# 1_-_Top.net
KiCad netlist of a schematic drawn in Altium Designer
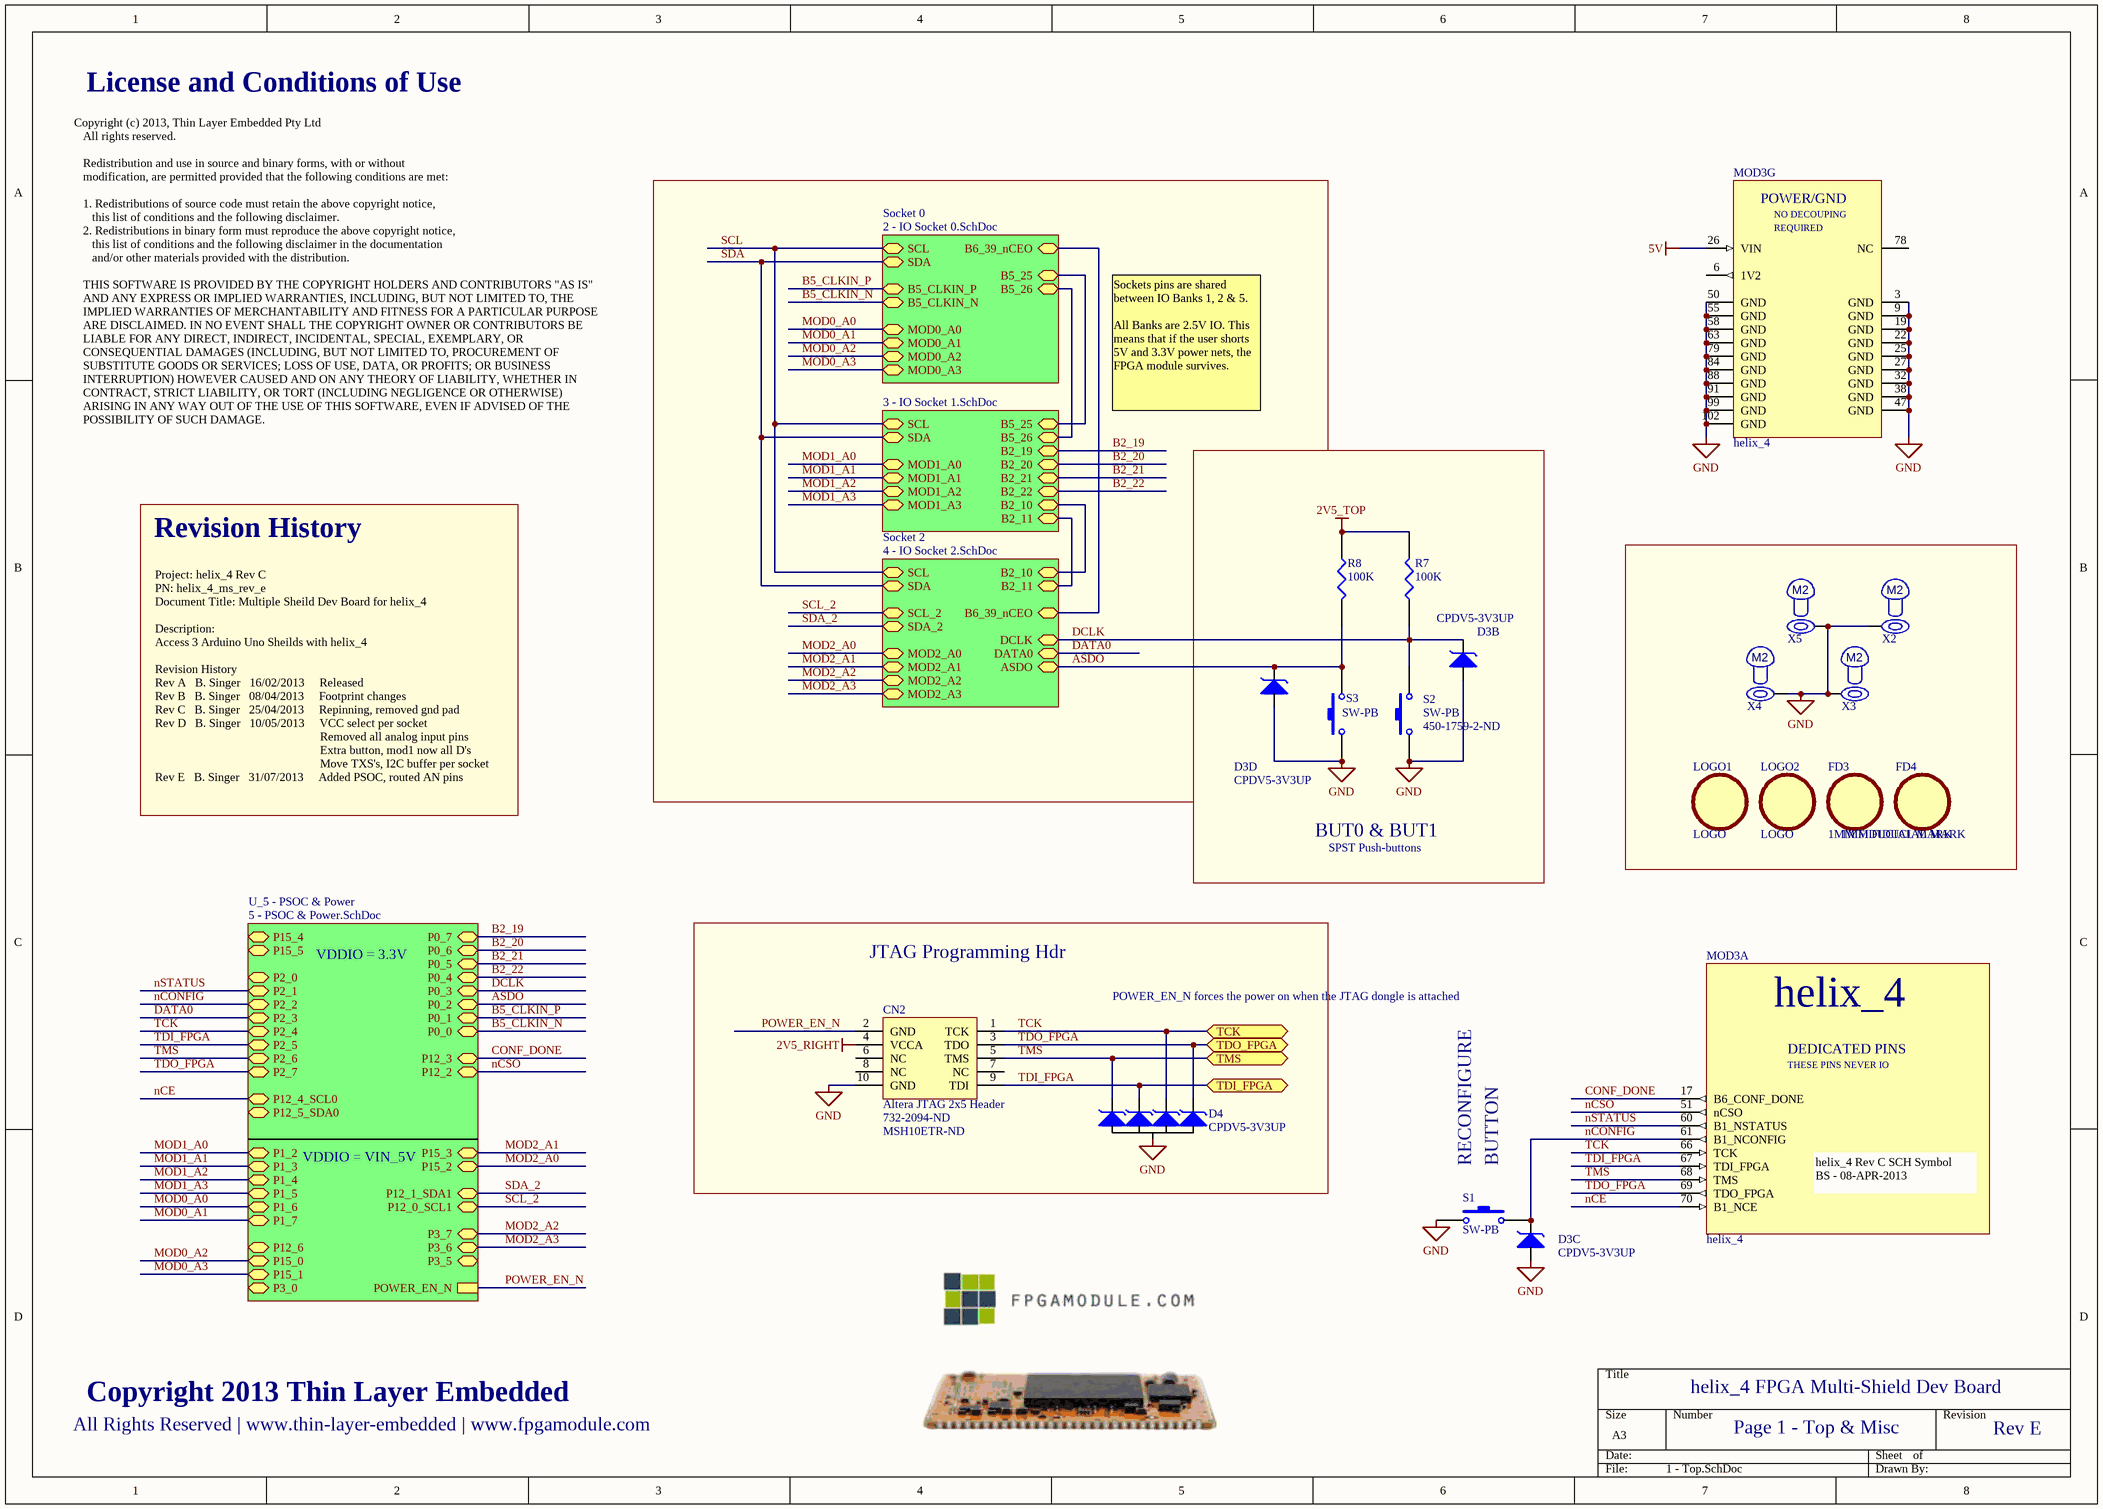
[diagram p0: 1 - Top.SchDoc]

(export (version "E")
  (design (tool "Eeschema 10.0.6"))
  (components
    (comp (ref "CN2")
      (value "Altera JTAG 2x5 Header")
      (footprint "BOXHDR2X5")
      (description "Header, 5-Pin, Dual row")
      (fields
        (field (name "MANUFACTURER") "Wurth Electronics Inc")
        (field (name "MANUFACTURER PART NUMBER") "61201021621")
        (field (name "SUPPLIER PART NUMBER 1") "732-2094-ND")
        (field (name "SUPPLIER PART NUMBER 2") "MSH10ETR-ND")
        (field (name "PUBLISHER") "Altium Limited")
      )
      (libsource (lib "master_library") (part "Altera JTAG 2x5 Header"))
    )
    (comp (ref "D3")
      (value "CPDV5-3V3UP")
      (footprint "sot-353")
      (description "4CH ESD DIODE 3V3/3.5V")
      (libsource (lib "master_library") (part "4CH ESD DIODE (SPLIT)"))
    )
    (comp (ref "D4")
      (value "CPDV5-3V3UP")
      (footprint "SOT-353")
      (description "4CH ESD DIODE 3V3/3.5V")
      (libsource (lib "master_library") (part "4CH ESD DIODE"))
    )
    (comp (ref "FD3") (value "1MM FIDUCIAL MARK") (footprint "FID_1MM") (libsource (lib "OB_1") (part "FID")))
    (comp (ref "FD4") (value "1MM FIDUCIAL MARK") (footprint "FID_1MM") (libsource (lib "OB_1") (part "FID")))
    (comp (ref "LOGO1") (value "LOGO") (footprint "LOGO_LARGE") (libsource (lib "OB_1") (part "FID")))
    (comp (ref "LOGO2") (value "LOGO") (footprint "LOGO_LARGE") (libsource (lib "OB_1") (part "FID")))
    (comp (ref "MOD3")
      (value "helix_4")
      (footprint "HELIX_4_LCC104_HOST")
      (libsource (lib "master_library") (part "helix_4 Rev C Module"))
    )
    (comp (ref "R7") (value "100K") (footprint "0805") (libsource (lib "*") (part "RES1")))
    (comp (ref "R8") (value "100K") (footprint "0805") (libsource (lib "*") (part "RES1")))
    (comp (ref "S1")
      (value "SW-PB")
      (footprint "FSM4JSMA")
      (description "Switch")
      (fields (field (name "PUBLISHER") "Altium Limited"))
      (libsource (lib "Miscellaneous Devices") (part "SW-PB"))
    )
    (comp (ref "S2")
      (value "SW-PB")
      (footprint "FSM4JSMA")
      (description "Switch")
      (fields (field (name "PUBLISHER") "Altium Limited"))
      (libsource (lib "Miscellaneous Devices") (part "SW-PB"))
    )
    (comp (ref "S3")
      (value "SW-PB")
      (footprint "FSM4JSMA")
      (description "Switch")
      (fields
        (field (name "SUPPLIER PART NUMBER 1") "450-1759-2-ND")
        (field (name "PUBLISHER") "Altium Limited")
      )
      (libsource (lib "Miscellaneous Devices") (part "SW-PB"))
    )
    (comp (ref "X2")
      (value "M2 Mounting Hole")
      (footprint "Mounting_Hole_M3")
      (description "Hole for M3 Screw")
      (libsource (lib "") (part "Mounting_Hole_M2_1"))
    )
    (comp (ref "X3")
      (value "M2 Mounting Hole")
      (footprint "Mounting_Hole_M3")
      (description "Hole for M3 Screw")
      (libsource (lib "") (part "Mounting_Hole_M2_1"))
    )
    (comp (ref "X4")
      (value "M2 Mounting Hole")
      (footprint "Mounting_Hole_M3")
      (description "Hole for M3 Screw")
      (libsource (lib "tea133-sch-2") (part "Mounting_Hole_M2"))
    )
    (comp (ref "X5")
      (value "M2 Mounting Hole")
      (footprint "Mounting_Hole_M3")
      (description "Hole for M3 Screw")
      (libsource (lib "tea133-sch-2") (part "Mounting_Hole_M2"))
    )
  )
  (nets
    (net (code "1") (name "/ASDO") (class "Default")
      (node (ref "D3") (pin "4") (pinfunction "K4_4") (pintype "passive"))
      (node (ref "R8") (pin "2") (pinfunction "2_2") (pintype "passive"))
      (node (ref "S3") (pin "2") (pinfunction "2_2") (pintype "passive"))
    )
    (net (code "13") (name "/CONF_DONE") (class "Default")
      (node (ref "MOD3") (pin "17") (pinfunction "B6_CONF_DONE_17") (pintype "output"))
    )
    (net (code "15") (name "/DCLK") (class "Default")
      (node (ref "D3") (pin "1") (pinfunction "K2_1") (pintype "passive"))
      (node (ref "R7") (pin "2") (pinfunction "2_2") (pintype "passive"))
      (node (ref "S2") (pin "2") (pinfunction "2_2") (pintype "passive"))
    )
    (net (code "35") (name "/POWER_EN_N") (class "Default")
      (node (ref "CN2") (pin "2") (pinfunction "GND_2") (pintype "passive"))
    )
    (net (code "40") (name "/TCK") (class "Default")
      (node (ref "CN2") (pin "1") (pinfunction "TCK_1") (pintype "passive"))
      (node (ref "D4") (pin "5") (pinfunction "K1_5") (pintype "passive"))
      (node (ref "MOD3") (pin "66") (pinfunction "TCK_66") (pintype "input"))
    )
    (net (code "41") (name "/TDI_FPGA") (class "Default")
      (node (ref "CN2") (pin "9") (pinfunction "TDI_9") (pintype "passive"))
      (node (ref "D4") (pin "1") (pinfunction "K2_1") (pintype "passive"))
      (node (ref "MOD3") (pin "67") (pinfunction "TDI_FPGA_67") (pintype "input"))
    )
    (net (code "42") (name "/TDO_FPGA") (class "Default")
      (node (ref "CN2") (pin "3") (pinfunction "TDO_3") (pintype "passive"))
      (node (ref "D4") (pin "4") (pinfunction "K2_4") (pintype "passive"))
      (node (ref "MOD3") (pin "69") (pinfunction "TDO_FPGA_69") (pintype "output"))
    )
    (net (code "43") (name "/TMS") (class "Default")
      (node (ref "CN2") (pin "5") (pinfunction "TMS_5") (pintype "passive"))
      (node (ref "D4") (pin "3") (pinfunction "K1_3") (pintype "passive"))
      (node (ref "MOD3") (pin "68") (pinfunction "TMS_68") (pintype "input"))
    )
    (net (code "44") (name "/nCE") (class "Default")
      (node (ref "MOD3") (pin "70") (pinfunction "B1_NCE_70") (pintype "input"))
    )
    (net (code "45") (name "/nCONFIG") (class "Default")
      (node (ref "D3") (pin "5") (pinfunction "K3_5") (pintype "passive"))
      (node (ref "MOD3") (pin "61") (pinfunction "B1_NCONFIG_61") (pintype "output"))
      (node (ref "S1") (pin "2") (pinfunction "2_2") (pintype "passive"))
    )
    (net (code "46") (name "/nCSO") (class "Default")
      (node (ref "MOD3") (pin "51") (pinfunction "nCSO_51") (pintype "output"))
    )
    (net (code "47") (name "/nSTATUS") (class "Default")
      (node (ref "MOD3") (pin "60") (pinfunction "B1_NSTATUS_60") (pintype "output"))
    )
    (net (code "48") (name "2V5_RIGHT") (class "Default")
      (node (ref "CN2") (pin "4") (pinfunction "VCCA_4") (pintype "passive"))
    )
    (net (code "49") (name "2V5_TOP") (class "Default")
      (node (ref "R7") (pin "1") (pinfunction "1_1") (pintype "passive"))
      (node (ref "R8") (pin "1") (pinfunction "1_1") (pintype "passive"))
    )
    (net (code "50") (name "5V") (class "Default")
      (node (ref "MOD3") (pin "26") (pinfunction "VIN_26") (pintype "input"))
    )
    (net (code "51") (name "GND") (class "Default")
      (node (ref "CN2") (pin "10") (pinfunction "GND_10") (pintype "passive"))
      (node (ref "D3") (pin "2") (pinfunction "A_2") (pintype "passive"))
      (node (ref "D4") (pin "2") (pinfunction "A_2") (pintype "passive"))
      (node (ref "MOD3") (pin "102") (pinfunction "GND_102") (pintype "passive"))
      (node (ref "MOD3") (pin "19") (pinfunction "GND_19") (pintype "passive"))
      (node (ref "MOD3") (pin "22") (pinfunction "GND_22") (pintype "passive"))
      (node (ref "MOD3") (pin "25") (pinfunction "GND_25") (pintype "passive"))
      (node (ref "MOD3") (pin "27") (pinfunction "GND_27") (pintype "passive"))
      (node (ref "MOD3") (pin "3") (pinfunction "GND_3") (pintype "passive"))
      (node (ref "MOD3") (pin "32") (pinfunction "GND_32") (pintype "passive"))
      (node (ref "MOD3") (pin "38") (pinfunction "GND_38") (pintype "passive"))
      (node (ref "MOD3") (pin "47") (pinfunction "GND_47") (pintype "passive"))
      (node (ref "MOD3") (pin "50") (pinfunction "GND_50") (pintype "passive"))
      (node (ref "MOD3") (pin "55") (pinfunction "GND_55") (pintype "passive"))
      (node (ref "MOD3") (pin "58") (pinfunction "GND_58") (pintype "passive"))
      (node (ref "MOD3") (pin "63") (pinfunction "GND_63") (pintype "passive"))
      (node (ref "MOD3") (pin "79") (pinfunction "GND_79") (pintype "passive"))
      (node (ref "MOD3") (pin "84") (pinfunction "GND_84") (pintype "passive"))
      (node (ref "MOD3") (pin "88") (pinfunction "GND_88") (pintype "passive"))
      (node (ref "MOD3") (pin "9") (pinfunction "GND_9") (pintype "passive"))
      (node (ref "MOD3") (pin "91") (pinfunction "GND_91") (pintype "passive"))
      (node (ref "MOD3") (pin "99") (pinfunction "GND_99") (pintype "passive"))
      (node (ref "S1") (pin "1") (pinfunction "1_1") (pintype "passive"))
      (node (ref "S2") (pin "1") (pinfunction "1_1") (pintype "passive"))
      (node (ref "S3") (pin "1") (pinfunction "1_1") (pintype "passive"))
      (node (ref "X2") (pin "1") (pinfunction "1_1") (pintype "passive"))
      (node (ref "X3") (pin "1") (pinfunction "1_1") (pintype "passive"))
      (node (ref "X4") (pin "1") (pinfunction "1_1") (pintype "passive"))
      (node (ref "X5") (pin "1") (pinfunction "1_1") (pintype "passive"))
    )
    (net (code "52") (name "unconnected-(CN2-NC-Pad6)") (class "Default")
      (node (ref "CN2") (pin "6") (pinfunction "NC_6") (pintype "passive"))
    )
    (net (code "53") (name "unconnected-(CN2-NC-Pad7)") (class "Default")
      (node (ref "CN2") (pin "7") (pinfunction "NC_7") (pintype "passive"))
    )
    (net (code "54") (name "unconnected-(CN2-NC-Pad8)") (class "Default")
      (node (ref "CN2") (pin "8") (pinfunction "NC_8") (pintype "passive"))
    )
    (net (code "55") (name "unconnected-(FD3-FID-Pad1)") (class "Default")
      (node (ref "FD3") (pin "1") (pinfunction "FID_1") (pintype "passive"))
    )
    (net (code "56") (name "unconnected-(FD4-FID-Pad1)") (class "Default")
      (node (ref "FD4") (pin "1") (pinfunction "FID_1") (pintype "passive"))
    )
    (net (code "57") (name "unconnected-(LOGO1-FID-Pad1)") (class "Default")
      (node (ref "LOGO1") (pin "1") (pinfunction "FID_1") (pintype "passive"))
    )
    (net (code "58") (name "unconnected-(LOGO2-FID-Pad1)") (class "Default")
      (node (ref "LOGO2") (pin "1") (pinfunction "FID_1") (pintype "passive"))
    )
    (net (code "59") (name "unconnected-(MOD3G-1V2-Pad6)") (class "Default")
      (node (ref "MOD3") (pin "6") (pinfunction "1V2_6") (pintype "output"))
    )
    (net (code "60") (name "unconnected-(MOD3G-NC-Pad78)") (class "Default")
      (node (ref "MOD3") (pin "78") (pinfunction "NC_78") (pintype "passive"))
    )
  )
)
